# clt.net
KiCad netlist of a schematic drawn in EAGLE
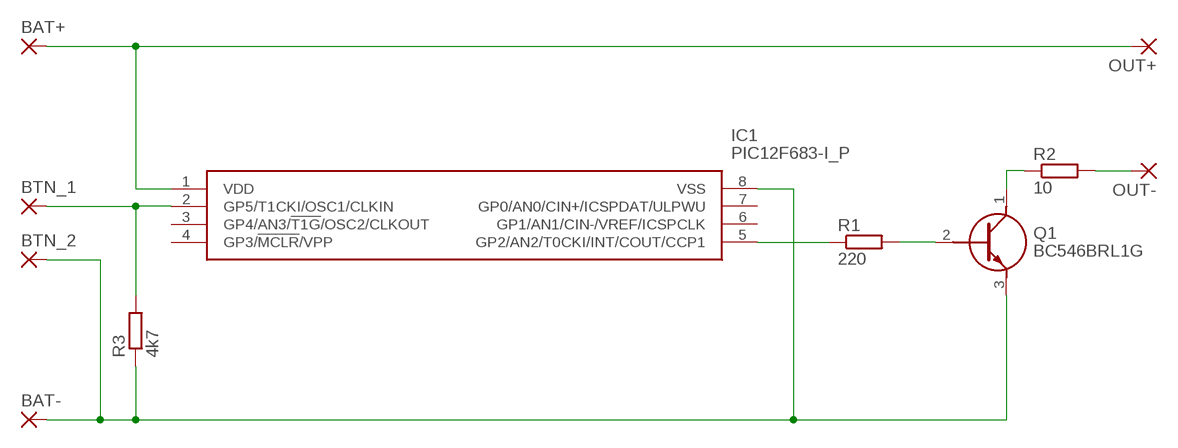
[diagram p0: schematic, sheet 1]

(export (version "E")
  (design (tool "Eeschema 10.0.6"))
  (components
    (comp (ref "BAT+")
      (value "2,54/0,9")
      (footprint "eagle-import:2,54_0,9")
      (libsource (lib "eagle-import") (part "2,54/0,9"))
    )
    (comp (ref "BAT-")
      (value "2,54/0,9")
      (footprint "eagle-import:2,54_0,9")
      (libsource (lib "eagle-import") (part "2,54/0,9"))
    )
    (comp (ref "BTN_1")
      (value "2,54/0,9")
      (footprint "eagle-import:2,54_0,9")
      (libsource (lib "eagle-import") (part "2,54/0,9"))
    )
    (comp (ref "BTN_2")
      (value "2,54/0,9")
      (footprint "eagle-import:2,54_0,9")
      (libsource (lib "eagle-import") (part "2,54/0,9"))
    )
    (comp (ref "IC1")
      (value "PIC12F683-I_P")
      (footprint "eagle-import:DIP781W56P254L950H533Q8N")
      (fields
        (field (name "MANUFACTURER_PART_NUMBER") "PIC12F683-I/P")
        (field (name "MOUSER_PART_NUMBER") "579-PIC12F683-I/P")
        (field (name "RS_PART_NUMBER") "8877151")
      )
      (libsource (lib "eagle-import") (part "PIC12F683-I_P"))
    )
    (comp (ref "OUT+")
      (value "2,54/0,9")
      (footprint "eagle-import:2,54_0,9")
      (libsource (lib "eagle-import") (part "2,54/0,9"))
    )
    (comp (ref "OUT-")
      (value "2,54/0,9")
      (footprint "eagle-import:2,54_0,9")
      (libsource (lib "eagle-import") (part "2,54/0,9"))
    )
    (comp (ref "Q1")
      (value "BC546BRL1G")
      (footprint "eagle-import:TO-92")
      (fields (field (name "MOUSER_PART_NUMBER") "863-BC546BRL1G") (field (name "RS_PART_NUMBER") "5449292P"))
      (libsource (lib "eagle-import") (part "BC546BRL1G"))
    )
    (comp (ref "R1")
      (value "220")
      (footprint "eagle-import:0204_5")
      (libsource (lib "eagle-import") (part "R-EU_0204/5"))
    )
    (comp (ref "R2")
      (value "10")
      (footprint "eagle-import:0204_5")
      (libsource (lib "eagle-import") (part "R-EU_0204/5"))
    )
    (comp (ref "R3")
      (value "4k7")
      (footprint "eagle-import:0204_5")
      (libsource (lib "eagle-import") (part "R-EU_0204/5"))
    )
  )
  (nets
    (net (code "1") (name "Net-(BAT+-P)") (class "Default")
      (node (ref "BAT+") (pin "1") (pinfunction "P_1") (pintype "passive"))
      (node (ref "IC1") (pin "1") (pinfunction "VDD_1") (pintype "power_in"))
      (node (ref "OUT+") (pin "1") (pinfunction "P_1") (pintype "passive"))
    )
    (net (code "2") (name "Net-(BAT--P)") (class "Default")
      (node (ref "BAT-") (pin "1") (pinfunction "P_1") (pintype "passive"))
      (node (ref "BTN_2") (pin "1") (pinfunction "P_1") (pintype "passive"))
      (node (ref "IC1") (pin "8") (pinfunction "VSS_8") (pintype "power_in"))
      (node (ref "Q1") (pin "3") (pinfunction "E_3") (pintype "bidirectional"))
      (node (ref "R3") (pin "1") (pinfunction "1_1") (pintype "passive"))
    )
    (net (code "3") (name "Net-(BTN_1-P)") (class "Default")
      (node (ref "BTN_1") (pin "1") (pinfunction "P_1") (pintype "passive"))
      (node (ref "IC1") (pin "2") (pinfunction "GP5/T1CKI/OSC1/CLKIN_2") (pintype "bidirectional"))
      (node (ref "R3") (pin "2") (pinfunction "2_2") (pintype "passive"))
    )
    (net (code "4") (name "Net-(IC1-GP2{slash}AN2{slash}T0CKI{slash}INT{slash}COUT{slash}CCP1)") (class "Default")
      (node (ref "IC1") (pin "5") (pinfunction "GP2/AN2/T0CKI/INT/COUT/CCP1_5") (pintype "output"))
      (node (ref "R1") (pin "1") (pinfunction "1_1") (pintype "passive"))
    )
    (net (code "5") (name "Net-(OUT--P)") (class "Default")
      (node (ref "OUT-") (pin "1") (pinfunction "P_1") (pintype "passive"))
      (node (ref "R2") (pin "2") (pinfunction "2_2") (pintype "passive"))
    )
    (net (code "6") (name "Net-(Q1-B)") (class "Default")
      (node (ref "Q1") (pin "2") (pinfunction "B_2") (pintype "bidirectional"))
      (node (ref "R1") (pin "2") (pinfunction "2_2") (pintype "passive"))
    )
    (net (code "7") (name "Net-(Q1-C)") (class "Default")
      (node (ref "Q1") (pin "1") (pinfunction "C_1") (pintype "bidirectional"))
      (node (ref "R2") (pin "1") (pinfunction "1_1") (pintype "passive"))
    )
    (net (code "8") (name "unconnected-(IC1-GP0{slash}AN0{slash}CIN+{slash}ICSPDAT{slash}ULPWU-Pad7)") (class "Default")
      (node (ref "IC1") (pin "7") (pinfunction "GP0/AN0/CIN+/ICSPDAT/ULPWU_7") (pintype "input"))
    )
    (net (code "9") (name "unconnected-(IC1-GP1{slash}AN1{slash}CIN-{slash}VREF{slash}ICSPCLK-Pad6)") (class "Default")
      (node (ref "IC1") (pin "6") (pinfunction "GP1/AN1/CIN-/VREF/ICSPCLK_6") (pintype "input"))
    )
    (net (code "10") (name "unconnected-(IC1-GP3{slash}~{MCLR}{slash}VPP-Pad4)") (class "Default")
      (node (ref "IC1") (pin "4") (pinfunction "GP3/~{MCLR}/VPP_4") (pintype "bidirectional"))
    )
    (net (code "11") (name "unconnected-(IC1-GP4{slash}AN3{slash}~{T1G}{slash}OSC2{slash}CLKOUT-Pad3)") (class "Default")
      (node (ref "IC1") (pin "3") (pinfunction "GP4/AN3/~{T1G}/OSC2/CLKOUT_3") (pintype "output"))
    )
  )
)
